# PWM_v2_1.net
KiCad netlist of a schematic drawn in EAGLE
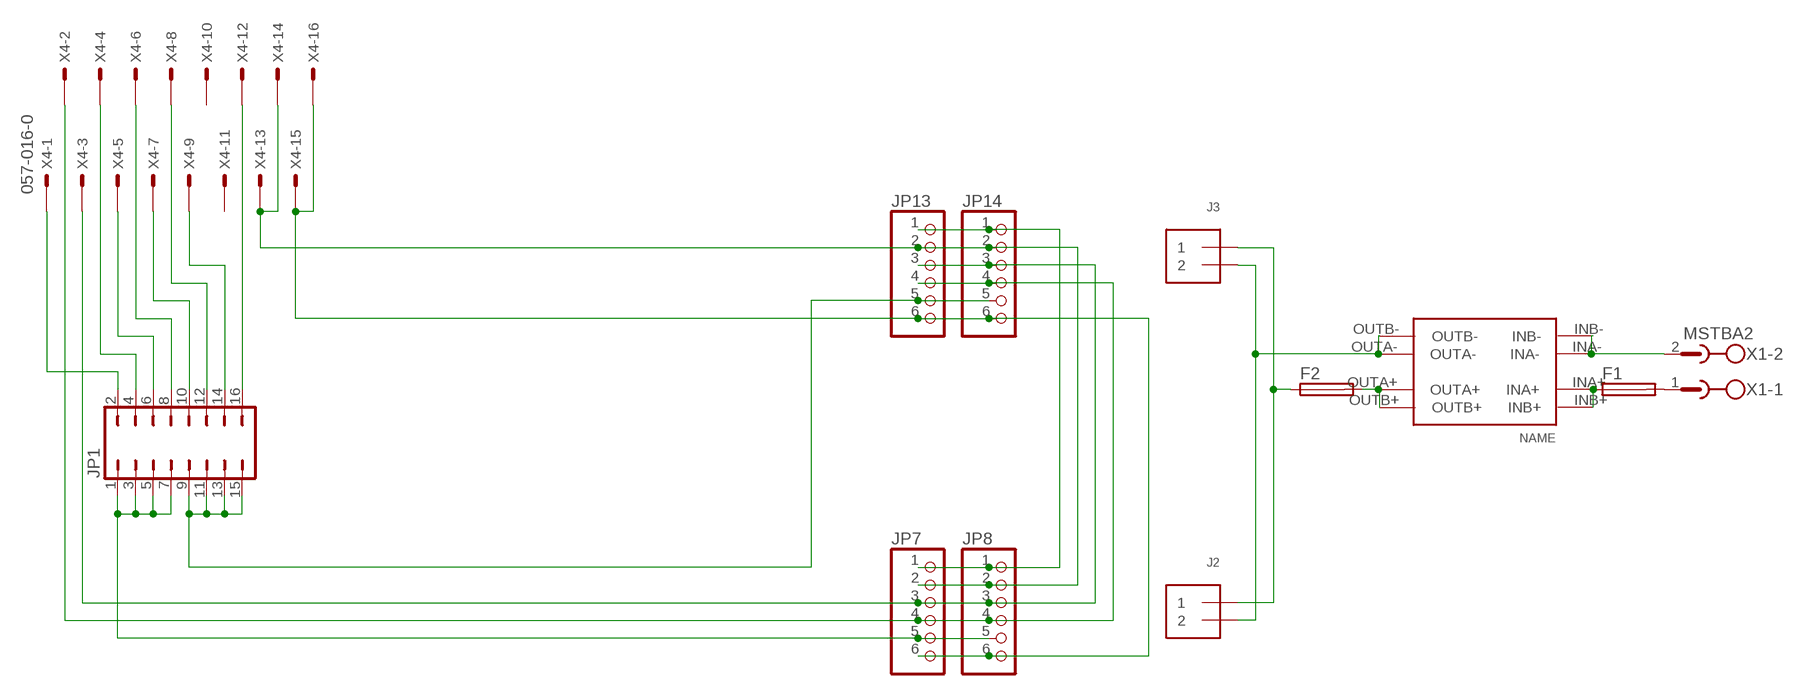
[diagram p0: schematic, sheet 1]

(export (version "E")
  (design (tool "Eeschema 10.0.6"))
  (components
    (comp (ref "F1")
      (value "SH25")
      (footprint "eagle-import:SH25")
      (fields (field (name "MF") "SCHURTER") (field (name "MPN") "0031.8211"))
      (libsource (lib "eagle-import") (part "SH25"))
    )
    (comp (ref "F2")
      (value "SH25")
      (footprint "eagle-import:SH25")
      (fields (field (name "MF") "SCHURTER") (field (name "MPN") "0031.8211"))
      (libsource (lib "eagle-import") (part "SH25"))
    )
    (comp (ref "J2")
      (value "TERMBLOCK_1X2")
      (footprint "eagle-import:TERMBLOCK_1X2-3.5MM")
      (libsource (lib "eagle-import") (part "TERMBLOCK_1X2"))
    )
    (comp (ref "J3")
      (value "TERMBLOCK_1X2")
      (footprint "eagle-import:TERMBLOCK_1X2-3.5MM")
      (libsource (lib "eagle-import") (part "TERMBLOCK_1X2"))
    )
    (comp (ref "JP1")
      (value "JP8Q")
      (footprint "eagle-import:JP8Q")
      (libsource (lib "eagle-import") (part "JP8Q"))
    )
    (comp (ref "JP7")
      (value "PINHD-1X6CB")
      (footprint "eagle-import:1X06-CLEANBIG")
      (libsource (lib "eagle-import") (part "PINHD-1X6CB"))
    )
    (comp (ref "JP8")
      (value "PINHD-1X6CB")
      (footprint "eagle-import:1X06-CLEANBIG")
      (libsource (lib "eagle-import") (part "PINHD-1X6CB"))
    )
    (comp (ref "JP13")
      (value "PINHD-1X6CB")
      (footprint "eagle-import:1X06-CLEANBIG")
      (libsource (lib "eagle-import") (part "PINHD-1X6CB"))
    )
    (comp (ref "JP14")
      (value "PINHD-1X6CB")
      (footprint "eagle-import:1X06-CLEANBIG")
      (libsource (lib "eagle-import") (part "PINHD-1X6CB"))
    )
    (comp (ref "U$2")
      (value "CP8-ADJ-B")
      (footprint "eagle-import:CP8-ADJ-B")
      (libsource (lib "eagle-import") (part "CP8-ADJ-B"))
    )
    (comp (ref "X1")
      (value "MSTBA2")
      (footprint "eagle-import:MSTBA2")
      (fields (field (name "MF") "FARNELL") (field (name "MPN") "1757242"))
      (libsource (lib "eagle-import") (part "MSTBA2"))
    )
    (comp (ref "X4")
      (value "057-016-0")
      (footprint "eagle-import:057-016-0")
      (libsource (lib "eagle-import") (part "057-016-0"))
    )
  )
  (nets
    (net (code "1") (name "Net-(F1-Pad1)") (class "Default")
      (node (ref "F1") (pin "1") (pinfunction "1_1") (pintype "passive"))
      (node (ref "U$2") (pin "INA+") (pinfunction "INA+_INA+") (pintype "passive"))
      (node (ref "U$2") (pin "INB+") (pinfunction "INB+_INB+") (pintype "passive"))
    )
    (net (code "2") (name "Net-(F1-Pad2)") (class "Default")
      (node (ref "F1") (pin "2") (pinfunction "2_2") (pintype "passive"))
      (node (ref "X1") (pin "1") (pinfunction "1_1") (pintype "passive"))
    )
    (net (code "3") (name "Net-(F2-Pad1)") (class "Default")
      (node (ref "F2") (pin "1") (pinfunction "1_1") (pintype "passive"))
      (node (ref "J2") (pin "1") (pinfunction "1_1") (pintype "passive"))
      (node (ref "J3") (pin "1") (pinfunction "1_1") (pintype "passive"))
    )
    (net (code "4") (name "Net-(F2-Pad2)") (class "Default")
      (node (ref "F2") (pin "2") (pinfunction "2_2") (pintype "passive"))
      (node (ref "U$2") (pin "OUTA+") (pinfunction "OUTA+_OUTA+") (pintype "passive"))
      (node (ref "U$2") (pin "OUTB+") (pinfunction "OUTB+_OUTB+") (pintype "passive"))
    )
    (net (code "5") (name "Net-(J2-Pad2)") (class "Default")
      (node (ref "J2") (pin "2") (pinfunction "2_2") (pintype "passive"))
      (node (ref "J3") (pin "2") (pinfunction "2_2") (pintype "passive"))
      (node (ref "U$2") (pin "OUTA-") (pinfunction "OUTA-_OUTA-") (pintype "passive"))
      (node (ref "U$2") (pin "OUTB-") (pinfunction "OUTB-_OUTB-") (pintype "bidirectional"))
    )
    (net (code "6") (name "Net-(JP1-Pad1)") (class "Default")
      (node (ref "JP1") (pin "1") (pinfunction "1_1") (pintype "passive"))
      (node (ref "JP1") (pin "3") (pinfunction "3_3") (pintype "passive"))
      (node (ref "JP1") (pin "5") (pinfunction "5_5") (pintype "passive"))
      (node (ref "JP1") (pin "7") (pinfunction "7_7") (pintype "passive"))
      (node (ref "JP7") (pin "5") (pinfunction "5_5") (pintype "passive"))
      (node (ref "JP8") (pin "5") (pinfunction "5_5") (pintype "passive"))
    )
    (net (code "7") (name "Net-(JP1-Pad11)") (class "Default")
      (node (ref "JP1") (pin "11") (pinfunction "11_11") (pintype "passive"))
      (node (ref "JP1") (pin "13") (pinfunction "13_13") (pintype "passive"))
      (node (ref "JP1") (pin "15") (pinfunction "15_15") (pintype "passive"))
      (node (ref "JP1") (pin "9") (pinfunction "9_9") (pintype "passive"))
      (node (ref "JP13") (pin "5") (pinfunction "5_5") (pintype "passive"))
      (node (ref "JP14") (pin "5") (pinfunction "5_5") (pintype "passive"))
    )
    (net (code "8") (name "Net-(JP13-Pad1)") (class "Default")
      (node (ref "JP13") (pin "1") (pinfunction "1_1") (pintype "passive"))
      (node (ref "JP14") (pin "1") (pinfunction "1_1") (pintype "passive"))
      (node (ref "JP7") (pin "1") (pinfunction "1_1") (pintype "passive"))
      (node (ref "JP8") (pin "1") (pinfunction "1_1") (pintype "passive"))
    )
    (net (code "9") (name "Net-(X1B-1)") (class "Default")
      (node (ref "U$2") (pin "INA-") (pinfunction "INA-_INA-") (pintype "passive"))
      (node (ref "U$2") (pin "INB-") (pinfunction "INB-_INB-") (pintype "passive"))
      (node (ref "X1") (pin "2") (pinfunction "1_2") (pintype "passive"))
    )
    (net (code "10") (name "Net-(X4A-S)") (class "Default")
      (node (ref "JP1") (pin "2") (pinfunction "2_2") (pintype "passive"))
      (node (ref "X4") (pin "1") (pinfunction "S_1") (pintype "passive"))
    )
    (net (code "11") (name "Net-(X4D-S)") (class "Default")
      (node (ref "JP1") (pin "16") (pinfunction "16_16") (pintype "passive"))
      (node (ref "X4") (pin "12") (pinfunction "S_12") (pintype "passive"))
    )
    (net (code "12") (name "Net-(X4E-S)") (class "Default")
      (node (ref "JP13") (pin "2") (pinfunction "2_2") (pintype "passive"))
      (node (ref "JP14") (pin "2") (pinfunction "2_2") (pintype "passive"))
      (node (ref "JP7") (pin "2") (pinfunction "2_2") (pintype "passive"))
      (node (ref "JP8") (pin "2") (pinfunction "2_2") (pintype "passive"))
      (node (ref "X4") (pin "13") (pinfunction "S_13") (pintype "passive"))
      (node (ref "X4") (pin "14") (pinfunction "S_14") (pintype "passive"))
    )
    (net (code "13") (name "Net-(X4G-S)") (class "Default")
      (node (ref "JP13") (pin "6") (pinfunction "6_6") (pintype "passive"))
      (node (ref "JP14") (pin "6") (pinfunction "6_6") (pintype "passive"))
      (node (ref "JP7") (pin "6") (pinfunction "6_6") (pintype "passive"))
      (node (ref "JP8") (pin "6") (pinfunction "6_6") (pintype "passive"))
      (node (ref "X4") (pin "15") (pinfunction "S_15") (pintype "passive"))
      (node (ref "X4") (pin "16") (pinfunction "S_16") (pintype "passive"))
    )
    (net (code "14") (name "Net-(X4I-S)") (class "Default")
      (node (ref "JP13") (pin "4") (pinfunction "4_4") (pintype "passive"))
      (node (ref "JP14") (pin "4") (pinfunction "4_4") (pintype "passive"))
      (node (ref "JP7") (pin "4") (pinfunction "4_4") (pintype "passive"))
      (node (ref "JP8") (pin "4") (pinfunction "4_4") (pintype "passive"))
      (node (ref "X4") (pin "2") (pinfunction "S_2") (pintype "passive"))
    )
    (net (code "15") (name "Net-(X4J-S)") (class "Default")
      (node (ref "JP13") (pin "3") (pinfunction "3_3") (pintype "passive"))
      (node (ref "JP14") (pin "3") (pinfunction "3_3") (pintype "passive"))
      (node (ref "JP7") (pin "3") (pinfunction "3_3") (pintype "passive"))
      (node (ref "JP8") (pin "3") (pinfunction "3_3") (pintype "passive"))
      (node (ref "X4") (pin "3") (pinfunction "S_3") (pintype "passive"))
    )
    (net (code "16") (name "Net-(X4K-S)") (class "Default")
      (node (ref "JP1") (pin "4") (pinfunction "4_4") (pintype "passive"))
      (node (ref "X4") (pin "4") (pinfunction "S_4") (pintype "passive"))
    )
    (net (code "17") (name "Net-(X4L-S)") (class "Default")
      (node (ref "JP1") (pin "6") (pinfunction "6_6") (pintype "passive"))
      (node (ref "X4") (pin "5") (pinfunction "S_5") (pintype "passive"))
    )
    (net (code "18") (name "Net-(X4M-S)") (class "Default")
      (node (ref "JP1") (pin "8") (pinfunction "8_8") (pintype "passive"))
      (node (ref "X4") (pin "6") (pinfunction "S_6") (pintype "passive"))
    )
    (net (code "19") (name "Net-(X4N-S)") (class "Default")
      (node (ref "JP1") (pin "10") (pinfunction "10_10") (pintype "passive"))
      (node (ref "X4") (pin "7") (pinfunction "S_7") (pintype "passive"))
    )
    (net (code "20") (name "Net-(X4O-S)") (class "Default")
      (node (ref "JP1") (pin "12") (pinfunction "12_12") (pintype "passive"))
      (node (ref "X4") (pin "8") (pinfunction "S_8") (pintype "passive"))
    )
    (net (code "21") (name "Net-(X4P-S)") (class "Default")
      (node (ref "JP1") (pin "14") (pinfunction "14_14") (pintype "passive"))
      (node (ref "X4") (pin "9") (pinfunction "S_9") (pintype "passive"))
    )
    (net (code "22") (name "unconnected-(X4B-S-Pad10)") (class "Default")
      (node (ref "X4") (pin "10") (pinfunction "S_10") (pintype "passive"))
    )
    (net (code "23") (name "unconnected-(X4C-S-Pad11)") (class "Default")
      (node (ref "X4") (pin "11") (pinfunction "S_11") (pintype "passive"))
    )
  )
)
